# Power.net
KiCad netlist of a schematic drawn in Altium Designer
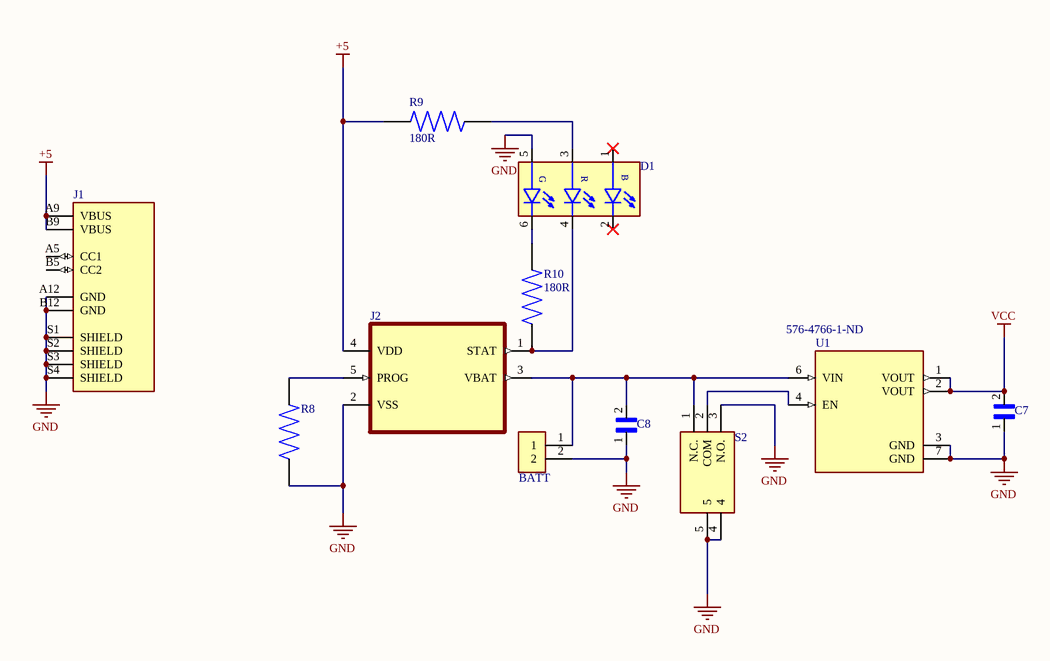
[diagram p0: Power.SchDoc]

(export (version "E")
  (design (tool "Eeschema 10.0.6"))
  (components
    (comp (ref "BATT")
      (value "~")
      (footprint "JST_B2B-PH-K-S(LF)(SN)")
      (description "Connector Header, PH Series, 2 Position, 2.00mm, Through Hole, Press-Fit, Solder, Natural")
      (fields (field (name "MANUFACTURER") "JST") (field (name "MANUFACTURER PART NUMBER") "B2BPHKSLFSN"))
      (libsource (lib "Mathcube_PCB") (part "B2B-PH-K-S(LF)(SN)"))
    )
    (comp (ref "C7")
      (value "~")
      (footprint "CAPC1608X90N")
      (description "Cap Ceramic 2.2uF 6.3V X7R 10% SMD 0603 125C Paper T/R")
      (fields
        (field (name "MANUFACTURER") "TDK")
        (field (name "MANUFACTURER PART NUMBER") "CGA3E1X7R0J225K080AC")
      )
      (libsource (lib "Mathcube_PCB") (part "CGA3E1X7R0J225K080AC"))
    )
    (comp (ref "C8")
      (value "~")
      (footprint "CAPC1608X90N")
      (description "Cap Ceramic 2.2uF 6.3V X7R 10% SMD 0603 125C Paper T/R")
      (fields
        (field (name "MANUFACTURER") "TDK")
        (field (name "MANUFACTURER PART NUMBER") "CGA3E1X7R0J225K080AC")
      )
      (libsource (lib "Mathcube_PCB") (part "CGA3E1X7R0J225K080AC"))
    )
    (comp (ref "D1")
      (value "~")
      (footprint "LED_QLS6B-FKW-CNSNSF043")
      (description "CREE - QLS6B-FKW-CNSNSF043 - FULL RANK, TAPE&REEL 07AH1280")
      (fields
        (field (name "MANUFACTURER") "Cree")
        (field (name "MANUFACTURER PART NUMBER") "QLS6B-FKW-CNSNSF043")
      )
      (libsource (lib "Mathcube_PCB") (part "QLS6B-FKW-CNSNSF043"))
    )
    (comp (ref "J1")
      (value "~")
      (footprint "GCT_USB4125-GF-A_REVA2")
      (description "USB Connector with 1.90mm shell stake length")
      (fields
        (field (name "MANUFACTURER") "Global Connector Technology")
        (field (name "MANUFACTURER PART NUMBER") "USB4125-GF-A-0190")
      )
      (libsource (lib "Mathcube_PCB") (part "USB4125-GF-A_REVA2"))
    )
    (comp (ref "J2")
      (value "~")
      (footprint "SOT95P280X145-5N")
      (description "MCP73831 Series Single-Cell Li-Ion/Li-Polymer Battery Charge Controller SOT-23-5")
      (fields
        (field (name "MANUFACTURER") "Microchip")
        (field (name "MANUFACTURER PART NUMBER") "MCP73831T-2ACI/OT")
      )
      (libsource (lib "Mathcube_PCB") (part "MCP73831T-2ACI/OT"))
    )
    (comp (ref "R8")
      (value "~")
      (footprint "RESC1005X40")
      (description "RES 10K OHM 5% 1/16W 0402")
      (fields
        (field (name "MANUFACTURER") "Stackpole Electronics")
        (field (name "MANUFACTURER PART NUMBER") "RMCF0402JT10K0")
      )
      (libsource (lib "Mathcube_PCB") (part "RMCF0402JT10K0"))
    )
    (comp (ref "R9")
      (value "180R")
      (footprint "RESC1005X40")
      (description "SMD Chip Resistor, 0402 [1005 Metric], 180 ohm, CRGCQ Series, 50 V, Thick Film, 63 mW")
      (fields
        (field (name "MANUFACTURER") "TE Connectivity")
        (field (name "MANUFACTURER PART NUMBER") "CRGCQ0402F180R")
      )
      (libsource (lib "Mathcube_PCB") (part "RMCF0402JT10K0_1"))
    )
    (comp (ref "R10")
      (value "180R")
      (footprint "RESC1005X40")
      (description "SMD Chip Resistor, 0402 [1005 Metric], 180 ohm, CRGCQ Series, 50 V, Thick Film, 63 mW")
      (fields
        (field (name "MANUFACTURER") "TE Connectivity")
        (field (name "MANUFACTURER PART NUMBER") "CRGCQ0402F180R")
      )
      (libsource (lib "Mathcube_PCB") (part "RMCF0402JT10K0_1"))
    )
    (comp (ref "S2")
      (value "~")
      (footprint "1101M2S3ABE2")
      (description "Switch Slide ON None ON SPDT Side Slide 6A 250VAC 28VDC PC Pins Bracket Mount/Through Hole")
      (fields
        (field (name "MANUFACTURER") "ITT C&K")
        (field (name "MANUFACTURER PART NUMBER") "1101M2S3AQE2")
      )
      (libsource (lib "Mathcube_PCB") (part "1101M2S3AQE2"))
    )
    (comp (ref "U1")
      (value "~")
      (footprint "SON40P120X120X60-7N")
      (description "LDO Regulator Pos 3.3V 0.5A 6-Pin TDFN EP T/R")
      (fields
        (field (name "SUPPLIER PART NUMBER 1") "576-4766-1-ND")
        (field (name "MANUFACTURER") "Microchip")
        (field (name "MANUFACTURER PART NUMBER") "MIC5528-3.3YMT-TR")
      )
      (libsource (lib "Mathcube_PCB") (part "MIC5528-3.3YMT-TR"))
    )
  )
  (nets
    (net (code "1") (name "+5") (class "Default")
      (node (ref "J1") (pin "A9") (pinfunction "VBUS_A9") (pintype "power_in"))
      (node (ref "J1") (pin "B9") (pinfunction "VBUS_B9") (pintype "power_in"))
      (node (ref "J2") (pin "4") (pinfunction "VDD_4") (pintype "power_in"))
      (node (ref "R9") (pin "1") (pinfunction "1_1") (pintype "passive"))
    )
    (net (code "2") (name "GND") (class "Default")
      (node (ref "BATT") (pin "2") (pinfunction "2_2") (pintype "passive"))
      (node (ref "C7") (pin "1") (pinfunction "1_1") (pintype "passive"))
      (node (ref "C8") (pin "1") (pinfunction "1_1") (pintype "passive"))
      (node (ref "D1") (pin "5") (pinfunction "GREEN_ANODE_5") (pintype "passive"))
      (node (ref "J1") (pin "A12") (pinfunction "GND_A12") (pintype "power_in"))
      (node (ref "J1") (pin "B12") (pinfunction "GND_B12") (pintype "power_in"))
      (node (ref "J1") (pin "S1") (pinfunction "SHIELD_S1") (pintype "passive"))
      (node (ref "J1") (pin "S2") (pinfunction "SHIELD_S2") (pintype "passive"))
      (node (ref "J1") (pin "S3") (pinfunction "SHIELD_S3") (pintype "passive"))
      (node (ref "J1") (pin "S4") (pinfunction "SHIELD_S4") (pintype "passive"))
      (node (ref "J2") (pin "2") (pinfunction "VSS_2") (pintype "power_in"))
      (node (ref "R8") (pin "2") (pinfunction "2_2") (pintype "passive"))
      (node (ref "S2") (pin "3") (pinfunction "N.O._3") (pintype "passive"))
      (node (ref "S2") (pin "4") (pinfunction "4_4") (pintype "passive"))
      (node (ref "S2") (pin "5") (pinfunction "5_5") (pintype "passive"))
      (node (ref "U1") (pin "3") (pinfunction "GND_3") (pintype "power_in"))
      (node (ref "U1") (pin "7") (pinfunction "GND_7") (pintype "power_in"))
    )
    (net (code "3") (name "Net-(D1-GREEN_CATHODE)") (class "Default")
      (node (ref "D1") (pin "6") (pinfunction "GREEN_CATHODE_6") (pintype "passive"))
      (node (ref "R10") (pin "2") (pinfunction "2_2") (pintype "passive"))
    )
    (net (code "4") (name "Net-(D1-RED_ANODE)") (class "Default")
      (node (ref "D1") (pin "3") (pinfunction "RED_ANODE_3") (pintype "passive"))
      (node (ref "R9") (pin "2") (pinfunction "2_2") (pintype "passive"))
    )
    (net (code "5") (name "Net-(D1-RED_CATHODE)") (class "Default")
      (node (ref "D1") (pin "4") (pinfunction "RED_CATHODE_4") (pintype "passive"))
      (node (ref "J2") (pin "1") (pinfunction "STAT_1") (pintype "output"))
      (node (ref "R10") (pin "1") (pinfunction "1_1") (pintype "passive"))
    )
    (net (code "6") (name "Net-(J2-PROG)") (class "Default")
      (node (ref "J2") (pin "5") (pinfunction "PROG_5") (pintype "input"))
      (node (ref "R8") (pin "1") (pinfunction "1_1") (pintype "passive"))
    )
    (net (code "7") (name "Net-(J2-VBAT)") (class "Default")
      (node (ref "BATT") (pin "1") (pinfunction "1_1") (pintype "passive"))
      (node (ref "C8") (pin "2") (pinfunction "2_2") (pintype "passive"))
      (node (ref "J2") (pin "3") (pinfunction "VBAT_3") (pintype "output"))
      (node (ref "S2") (pin "1") (pinfunction "N.C._1") (pintype "passive"))
      (node (ref "U1") (pin "6") (pinfunction "VIN_6") (pintype "input"))
    )
    (net (code "8") (name "Net-(S2-COM)") (class "Default")
      (node (ref "S2") (pin "2") (pinfunction "COM_2") (pintype "passive"))
      (node (ref "U1") (pin "4") (pinfunction "EN_4") (pintype "input"))
    )
    (net (code "9") (name "VCC") (class "Default")
      (node (ref "C7") (pin "2") (pinfunction "2_2") (pintype "passive"))
      (node (ref "U1") (pin "1") (pinfunction "VOUT_1") (pintype "output"))
      (node (ref "U1") (pin "2") (pinfunction "VOUT_2") (pintype "output"))
    )
    (net (code "10") (name "unconnected-(D1-BLUE_ANODE-Pad1)") (class "Default")
      (node (ref "D1") (pin "1") (pinfunction "BLUE_ANODE_1") (pintype "passive+no_connect"))
    )
    (net (code "11") (name "unconnected-(D1-BLUE_CATHODE-Pad2)") (class "Default")
      (node (ref "D1") (pin "2") (pinfunction "BLUE_CATHODE_2") (pintype "passive+no_connect"))
    )
    (net (code "12") (name "unconnected-(J1-CC1-PadA5)") (class "Default")
      (node (ref "J1") (pin "A5") (pinfunction "CC1_A5") (pintype "bidirectional"))
    )
    (net (code "13") (name "unconnected-(J1-CC2-PadB5)") (class "Default")
      (node (ref "J1") (pin "B5") (pinfunction "CC2_B5") (pintype "bidirectional"))
    )
  )
)
